# stabs.net
KiCad netlist of a schematic drawn in Altium Designer
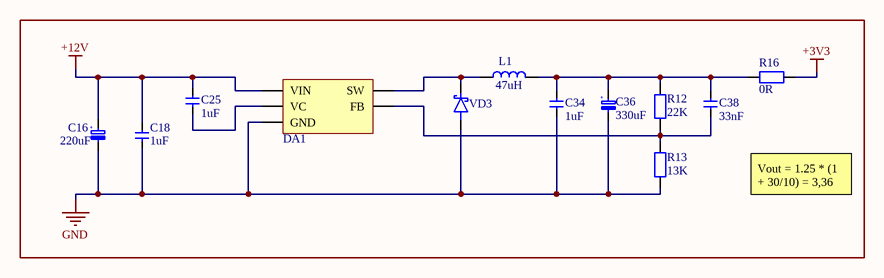
[diagram p0: stabs.SchDoc]

(export (version "E")
  (design (tool "Eeschema 10.0.6"))
  (components
    (comp (ref "C16")
      (value "220uF")
      (footprint "D8C3.2H12")
      (description "50V")
      (libsource (lib "GKirik") (part "Cap Aluminum"))
    )
    (comp (ref "C18")
      (value "1uF")
      (footprint "CAP0805")
      (description "Ceramic SMD Cap")
      (libsource (lib "Asterisk") (part "CAP Ceramic"))
    )
    (comp (ref "C25")
      (value "1uF")
      (footprint "CAP0805")
      (description "Ceramic SMD Cap")
      (libsource (lib "Asterisk") (part "CAP Ceramic"))
    )
    (comp (ref "C34")
      (value "1uF")
      (footprint "CAP0805")
      (description "Ceramic SMD Cap")
      (libsource (lib "Asterisk") (part "CAP Ceramic"))
    )
    (comp (ref "C36")
      (value "330uF")
      (footprint "D10C4.4H10")
      (description "25V")
      (libsource (lib "GKirik") (part "Cap Aluminum"))
    )
    (comp (ref "C38")
      (value "33nF")
      (footprint "CAP0805")
      (description "Ceramic SMD Cap")
      (libsource (lib "Asterisk") (part "CAP Ceramic"))
    )
    (comp (ref "DA1")
      (value "XL4015")
      (footprint "TO263-5L")
      (description "Buck converter")
      (libsource (lib "Asterisk") (part "XL4015"))
    )
    (comp (ref "L1") (value "47uH") (footprint "IND: B82477G") (libsource (lib "GKirik") (part "Inductor")))
    (comp (ref "R12")
      (value "22K")
      (footprint "RES0805")
      (description "RES smd")
      (libsource (lib "Asterisk") (part "RES"))
    )
    (comp (ref "R13")
      (value "13K")
      (footprint "RES0805")
      (description "RES smd")
      (libsource (lib "Asterisk") (part "RES"))
    )
    (comp (ref "R16")
      (value "0R")
      (footprint "RES1206")
      (description "RES smd")
      (libsource (lib "Asterisk") (part "RES"))
    )
    (comp (ref "VD3")
      (value "Diode Schottky")
      (footprint "DO-214AC (SMA)")
      (libsource (lib "Asterisk") (part "Diode Schottky"))
    )
  )
  (nets
    (net (code "1") (name "+3V3") (class "Default")
      (node (ref "R16") (pin "2") (pinfunction "2_2") (pintype "passive"))
    )
    (net (code "2") (name "+12V") (class "Default")
      (node (ref "C16") (pin "1") (pinfunction "PLUS_1") (pintype "passive"))
      (node (ref "C18") (pin "2") (pinfunction "2_2") (pintype "passive"))
      (node (ref "C25") (pin "2") (pinfunction "2_2") (pintype "passive"))
      (node (ref "DA1") (pin "5") (pinfunction "VIN_5") (pintype "passive"))
    )
    (net (code "3") (name "GND") (class "Default")
      (node (ref "C16") (pin "2") (pinfunction "MINUS_2") (pintype "passive"))
      (node (ref "C18") (pin "1") (pinfunction "1_1") (pintype "passive"))
      (node (ref "C34") (pin "1") (pinfunction "1_1") (pintype "passive"))
      (node (ref "C36") (pin "2") (pinfunction "MINUS_2") (pintype "passive"))
      (node (ref "DA1") (pin "1") (pinfunction "GND_1") (pintype "passive"))
      (node (ref "R13") (pin "1") (pinfunction "1_1") (pintype "passive"))
      (node (ref "VD3") (pin "A") (pinfunction "A_A") (pintype "passive"))
    )
    (net (code "4") (name "Net-(C36-PLUS)") (class "Default")
      (node (ref "C34") (pin "2") (pinfunction "2_2") (pintype "passive"))
      (node (ref "C36") (pin "1") (pinfunction "PLUS_1") (pintype "passive"))
      (node (ref "C38") (pin "2") (pinfunction "2_2") (pintype "passive"))
      (node (ref "L1") (pin "2") (pinfunction "2_2") (pintype "passive"))
      (node (ref "R12") (pin "2") (pinfunction "2_2") (pintype "passive"))
      (node (ref "R16") (pin "1") (pinfunction "1_1") (pintype "passive"))
    )
    (net (code "5") (name "Net-(DA1-FB)") (class "Default")
      (node (ref "C38") (pin "1") (pinfunction "1_1") (pintype "passive"))
      (node (ref "DA1") (pin "2") (pinfunction "FB_2") (pintype "passive"))
      (node (ref "R12") (pin "1") (pinfunction "1_1") (pintype "passive"))
      (node (ref "R13") (pin "2") (pinfunction "2_2") (pintype "passive"))
    )
    (net (code "6") (name "Net-(DA1-SW)") (class "Default")
      (node (ref "DA1") (pin "3") (pinfunction "SW_3") (pintype "passive"))
      (node (ref "L1") (pin "1") (pinfunction "1_1") (pintype "passive"))
      (node (ref "VD3") (pin "K") (pinfunction "K_K") (pintype "passive"))
    )
    (net (code "7") (name "Net-(DA1-VC)") (class "Default")
      (node (ref "C25") (pin "1") (pinfunction "1_1") (pintype "passive"))
      (node (ref "DA1") (pin "4") (pinfunction "VC_4") (pintype "passive"))
    )
  )
)
